# charliewatch.net
KiCad netlist of a schematic drawn in EAGLE
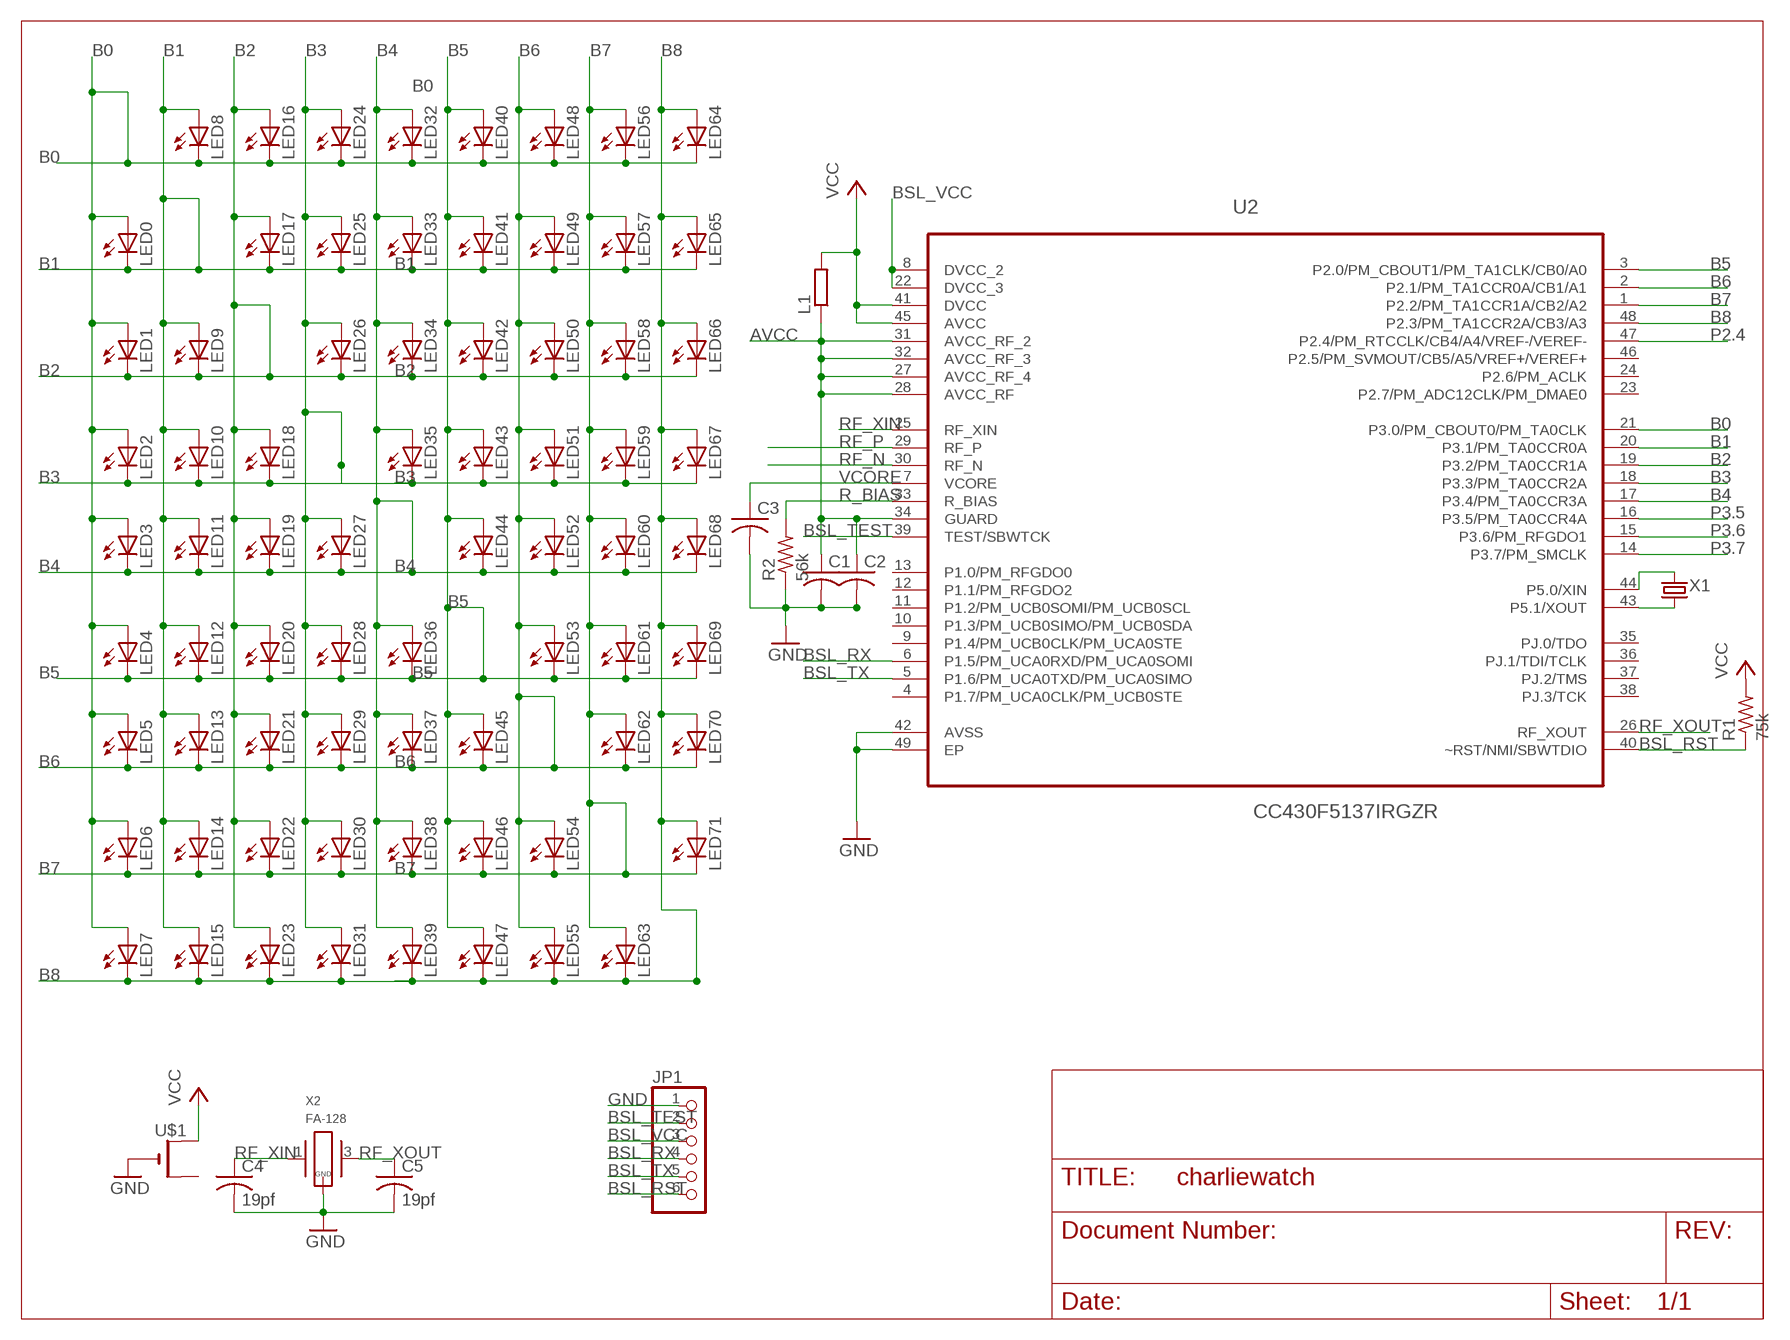
[diagram p0: schematic, sheet 1]

(export (version "E")
  (design (tool "Eeschema 10.0.6"))
  (components
    (comp (ref "C1")
      (value "C-USC0603")
      (footprint "eagle-import:C0603")
      (libsource (lib "eagle-import") (part "C-USC0603"))
    )
    (comp (ref "C2")
      (value "C-USC0603")
      (footprint "eagle-import:C0603")
      (libsource (lib "eagle-import") (part "C-USC0603"))
    )
    (comp (ref "C3")
      (value "C-USC0603")
      (footprint "eagle-import:C0603")
      (libsource (lib "eagle-import") (part "C-USC0603"))
    )
    (comp (ref "C4")
      (value "19pf")
      (footprint "eagle-import:C0603")
      (libsource (lib "eagle-import") (part "C-USC0603"))
    )
    (comp (ref "C5")
      (value "19pf")
      (footprint "eagle-import:C0603")
      (libsource (lib "eagle-import") (part "C-USC0603"))
    )
    (comp (ref "JP1")
      (value "PINHD-1X6LOCK")
      (footprint "eagle-import:1X06-BIGLOCK")
      (libsource (lib "eagle-import") (part "PINHD-1X6LOCK"))
    )
    (comp (ref "L1")
      (value "R-EU_R0603")
      (footprint "eagle-import:R0603")
      (libsource (lib "eagle-import") (part "R-EU_R0603"))
    )
    (comp (ref "LED0")
      (value "LEDCHIPLED_0603")
      (footprint "eagle-import:CHIPLED_0603")
      (libsource (lib "eagle-import") (part "LEDCHIPLED_0603"))
    )
    (comp (ref "LED1")
      (value "LEDCHIPLED_0603")
      (footprint "eagle-import:CHIPLED_0603")
      (libsource (lib "eagle-import") (part "LEDCHIPLED_0603"))
    )
    (comp (ref "LED2")
      (value "LEDCHIPLED_0603")
      (footprint "eagle-import:CHIPLED_0603")
      (libsource (lib "eagle-import") (part "LEDCHIPLED_0603"))
    )
    (comp (ref "LED3")
      (value "LEDCHIPLED_0603")
      (footprint "eagle-import:CHIPLED_0603")
      (libsource (lib "eagle-import") (part "LEDCHIPLED_0603"))
    )
    (comp (ref "LED4")
      (value "LEDCHIPLED_0603")
      (footprint "eagle-import:CHIPLED_0603")
      (libsource (lib "eagle-import") (part "LEDCHIPLED_0603"))
    )
    (comp (ref "LED5")
      (value "LEDCHIPLED_0603")
      (footprint "eagle-import:CHIPLED_0603")
      (libsource (lib "eagle-import") (part "LEDCHIPLED_0603"))
    )
    (comp (ref "LED6")
      (value "LEDCHIPLED_0603")
      (footprint "eagle-import:CHIPLED_0603")
      (libsource (lib "eagle-import") (part "LEDCHIPLED_0603"))
    )
    (comp (ref "LED7")
      (value "LEDCHIPLED_0603")
      (footprint "eagle-import:CHIPLED_0603")
      (libsource (lib "eagle-import") (part "LEDCHIPLED_0603"))
    )
    (comp (ref "LED8")
      (value "LEDCHIPLED_0603")
      (footprint "eagle-import:CHIPLED_0603")
      (libsource (lib "eagle-import") (part "LEDCHIPLED_0603"))
    )
    (comp (ref "LED9")
      (value "LEDCHIPLED_0603")
      (footprint "eagle-import:CHIPLED_0603")
      (libsource (lib "eagle-import") (part "LEDCHIPLED_0603"))
    )
    (comp (ref "LED10")
      (value "LEDCHIPLED_0603")
      (footprint "eagle-import:CHIPLED_0603")
      (libsource (lib "eagle-import") (part "LEDCHIPLED_0603"))
    )
    (comp (ref "LED11")
      (value "LEDCHIPLED_0603")
      (footprint "eagle-import:CHIPLED_0603")
      (libsource (lib "eagle-import") (part "LEDCHIPLED_0603"))
    )
    (comp (ref "LED12")
      (value "LEDCHIPLED_0603")
      (footprint "eagle-import:CHIPLED_0603")
      (libsource (lib "eagle-import") (part "LEDCHIPLED_0603"))
    )
    (comp (ref "LED13")
      (value "LEDCHIPLED_0603")
      (footprint "eagle-import:CHIPLED_0603")
      (libsource (lib "eagle-import") (part "LEDCHIPLED_0603"))
    )
    (comp (ref "LED14")
      (value "LEDCHIPLED_0603")
      (footprint "eagle-import:CHIPLED_0603")
      (libsource (lib "eagle-import") (part "LEDCHIPLED_0603"))
    )
    (comp (ref "LED15")
      (value "LEDCHIPLED_0603")
      (footprint "eagle-import:CHIPLED_0603")
      (libsource (lib "eagle-import") (part "LEDCHIPLED_0603"))
    )
    (comp (ref "LED16")
      (value "LEDCHIPLED_0603")
      (footprint "eagle-import:CHIPLED_0603")
      (libsource (lib "eagle-import") (part "LEDCHIPLED_0603"))
    )
    (comp (ref "LED17")
      (value "LEDCHIPLED_0603")
      (footprint "eagle-import:CHIPLED_0603")
      (libsource (lib "eagle-import") (part "LEDCHIPLED_0603"))
    )
    (comp (ref "LED18")
      (value "LEDCHIPLED_0603")
      (footprint "eagle-import:CHIPLED_0603")
      (libsource (lib "eagle-import") (part "LEDCHIPLED_0603"))
    )
    (comp (ref "LED19")
      (value "LEDCHIPLED_0603")
      (footprint "eagle-import:CHIPLED_0603")
      (libsource (lib "eagle-import") (part "LEDCHIPLED_0603"))
    )
    (comp (ref "LED20")
      (value "LEDCHIPLED_0603")
      (footprint "eagle-import:CHIPLED_0603")
      (libsource (lib "eagle-import") (part "LEDCHIPLED_0603"))
    )
    (comp (ref "LED21")
      (value "LEDCHIPLED_0603")
      (footprint "eagle-import:CHIPLED_0603")
      (libsource (lib "eagle-import") (part "LEDCHIPLED_0603"))
    )
    (comp (ref "LED22")
      (value "LEDCHIPLED_0603")
      (footprint "eagle-import:CHIPLED_0603")
      (libsource (lib "eagle-import") (part "LEDCHIPLED_0603"))
    )
    (comp (ref "LED23")
      (value "LEDCHIPLED_0603")
      (footprint "eagle-import:CHIPLED_0603")
      (libsource (lib "eagle-import") (part "LEDCHIPLED_0603"))
    )
    (comp (ref "LED24")
      (value "LEDCHIPLED_0603")
      (footprint "eagle-import:CHIPLED_0603")
      (libsource (lib "eagle-import") (part "LEDCHIPLED_0603"))
    )
    (comp (ref "LED25")
      (value "LEDCHIPLED_0603")
      (footprint "eagle-import:CHIPLED_0603")
      (libsource (lib "eagle-import") (part "LEDCHIPLED_0603"))
    )
    (comp (ref "LED26")
      (value "LEDCHIPLED_0603")
      (footprint "eagle-import:CHIPLED_0603")
      (libsource (lib "eagle-import") (part "LEDCHIPLED_0603"))
    )
    (comp (ref "LED27")
      (value "LEDCHIPLED_0603")
      (footprint "eagle-import:CHIPLED_0603")
      (libsource (lib "eagle-import") (part "LEDCHIPLED_0603"))
    )
    (comp (ref "LED28")
      (value "LEDCHIPLED_0603")
      (footprint "eagle-import:CHIPLED_0603")
      (libsource (lib "eagle-import") (part "LEDCHIPLED_0603"))
    )
    (comp (ref "LED29")
      (value "LEDCHIPLED_0603")
      (footprint "eagle-import:CHIPLED_0603")
      (libsource (lib "eagle-import") (part "LEDCHIPLED_0603"))
    )
    (comp (ref "LED30")
      (value "LEDCHIPLED_0603")
      (footprint "eagle-import:CHIPLED_0603")
      (libsource (lib "eagle-import") (part "LEDCHIPLED_0603"))
    )
    (comp (ref "LED31")
      (value "LEDCHIPLED_0603")
      (footprint "eagle-import:CHIPLED_0603")
      (libsource (lib "eagle-import") (part "LEDCHIPLED_0603"))
    )
    (comp (ref "LED32")
      (value "LEDCHIPLED_0603")
      (footprint "eagle-import:CHIPLED_0603")
      (libsource (lib "eagle-import") (part "LEDCHIPLED_0603"))
    )
    (comp (ref "LED33")
      (value "LEDCHIPLED_0603")
      (footprint "eagle-import:CHIPLED_0603")
      (libsource (lib "eagle-import") (part "LEDCHIPLED_0603"))
    )
    (comp (ref "LED34")
      (value "LEDCHIPLED_0603")
      (footprint "eagle-import:CHIPLED_0603")
      (libsource (lib "eagle-import") (part "LEDCHIPLED_0603"))
    )
    (comp (ref "LED35")
      (value "LEDCHIPLED_0603")
      (footprint "eagle-import:CHIPLED_0603")
      (libsource (lib "eagle-import") (part "LEDCHIPLED_0603"))
    )
    (comp (ref "LED36")
      (value "LEDCHIPLED_0603")
      (footprint "eagle-import:CHIPLED_0603")
      (libsource (lib "eagle-import") (part "LEDCHIPLED_0603"))
    )
    (comp (ref "LED37")
      (value "LEDCHIPLED_0603")
      (footprint "eagle-import:CHIPLED_0603")
      (libsource (lib "eagle-import") (part "LEDCHIPLED_0603"))
    )
    (comp (ref "LED38")
      (value "LEDCHIPLED_0603")
      (footprint "eagle-import:CHIPLED_0603")
      (libsource (lib "eagle-import") (part "LEDCHIPLED_0603"))
    )
    (comp (ref "LED39")
      (value "LEDCHIPLED_0603")
      (footprint "eagle-import:CHIPLED_0603")
      (libsource (lib "eagle-import") (part "LEDCHIPLED_0603"))
    )
    (comp (ref "LED40")
      (value "LEDCHIPLED_0603")
      (footprint "eagle-import:CHIPLED_0603")
      (libsource (lib "eagle-import") (part "LEDCHIPLED_0603"))
    )
    (comp (ref "LED41")
      (value "LEDCHIPLED_0603")
      (footprint "eagle-import:CHIPLED_0603")
      (libsource (lib "eagle-import") (part "LEDCHIPLED_0603"))
    )
    (comp (ref "LED42")
      (value "LEDCHIPLED_0603")
      (footprint "eagle-import:CHIPLED_0603")
      (libsource (lib "eagle-import") (part "LEDCHIPLED_0603"))
    )
    (comp (ref "LED43")
      (value "LEDCHIPLED_0603")
      (footprint "eagle-import:CHIPLED_0603")
      (libsource (lib "eagle-import") (part "LEDCHIPLED_0603"))
    )
    (comp (ref "LED44")
      (value "LEDCHIPLED_0603")
      (footprint "eagle-import:CHIPLED_0603")
      (libsource (lib "eagle-import") (part "LEDCHIPLED_0603"))
    )
    (comp (ref "LED45")
      (value "LEDCHIPLED_0603")
      (footprint "eagle-import:CHIPLED_0603")
      (libsource (lib "eagle-import") (part "LEDCHIPLED_0603"))
    )
    (comp (ref "LED46")
      (value "LEDCHIPLED_0603")
      (footprint "eagle-import:CHIPLED_0603")
      (libsource (lib "eagle-import") (part "LEDCHIPLED_0603"))
    )
    (comp (ref "LED47")
      (value "LEDCHIPLED_0603")
      (footprint "eagle-import:CHIPLED_0603")
      (libsource (lib "eagle-import") (part "LEDCHIPLED_0603"))
    )
    (comp (ref "LED48")
      (value "LEDCHIPLED_0603")
      (footprint "eagle-import:CHIPLED_0603")
      (libsource (lib "eagle-import") (part "LEDCHIPLED_0603"))
    )
    (comp (ref "LED49")
      (value "LEDCHIPLED_0603")
      (footprint "eagle-import:CHIPLED_0603")
      (libsource (lib "eagle-import") (part "LEDCHIPLED_0603"))
    )
    (comp (ref "LED50")
      (value "LEDCHIPLED_0603")
      (footprint "eagle-import:CHIPLED_0603")
      (libsource (lib "eagle-import") (part "LEDCHIPLED_0603"))
    )
    (comp (ref "LED51")
      (value "LEDCHIPLED_0603")
      (footprint "eagle-import:CHIPLED_0603")
      (libsource (lib "eagle-import") (part "LEDCHIPLED_0603"))
    )
    (comp (ref "LED52")
      (value "LEDCHIPLED_0603")
      (footprint "eagle-import:CHIPLED_0603")
      (libsource (lib "eagle-import") (part "LEDCHIPLED_0603"))
    )
    (comp (ref "LED53")
      (value "LEDCHIPLED_0603")
      (footprint "eagle-import:CHIPLED_0603")
      (libsource (lib "eagle-import") (part "LEDCHIPLED_0603"))
    )
    (comp (ref "LED54")
      (value "LEDCHIPLED_0603")
      (footprint "eagle-import:CHIPLED_0603")
      (libsource (lib "eagle-import") (part "LEDCHIPLED_0603"))
    )
    (comp (ref "LED55")
      (value "LEDCHIPLED_0603")
      (footprint "eagle-import:CHIPLED_0603")
      (libsource (lib "eagle-import") (part "LEDCHIPLED_0603"))
    )
    (comp (ref "LED56")
      (value "LEDCHIPLED_0603")
      (footprint "eagle-import:CHIPLED_0603")
      (libsource (lib "eagle-import") (part "LEDCHIPLED_0603"))
    )
    (comp (ref "LED57")
      (value "LEDCHIPLED_0603")
      (footprint "eagle-import:CHIPLED_0603")
      (libsource (lib "eagle-import") (part "LEDCHIPLED_0603"))
    )
    (comp (ref "LED58")
      (value "LEDCHIPLED_0603")
      (footprint "eagle-import:CHIPLED_0603")
      (libsource (lib "eagle-import") (part "LEDCHIPLED_0603"))
    )
    (comp (ref "LED59")
      (value "LEDCHIPLED_0603")
      (footprint "eagle-import:CHIPLED_0603")
      (libsource (lib "eagle-import") (part "LEDCHIPLED_0603"))
    )
    (comp (ref "LED60")
      (value "LEDCHIPLED_0603")
      (footprint "eagle-import:CHIPLED_0603")
      (libsource (lib "eagle-import") (part "LEDCHIPLED_0603"))
    )
    (comp (ref "LED61")
      (value "LEDCHIPLED_0603")
      (footprint "eagle-import:CHIPLED_0603")
      (libsource (lib "eagle-import") (part "LEDCHIPLED_0603"))
    )
    (comp (ref "LED62")
      (value "LEDCHIPLED_0603")
      (footprint "eagle-import:CHIPLED_0603")
      (libsource (lib "eagle-import") (part "LEDCHIPLED_0603"))
    )
    (comp (ref "LED63")
      (value "LEDCHIPLED_0603")
      (footprint "eagle-import:CHIPLED_0603")
      (libsource (lib "eagle-import") (part "LEDCHIPLED_0603"))
    )
    (comp (ref "LED64")
      (value "LEDCHIPLED_0603")
      (footprint "eagle-import:CHIPLED_0603")
      (libsource (lib "eagle-import") (part "LEDCHIPLED_0603"))
    )
    (comp (ref "LED65")
      (value "LEDCHIPLED_0603")
      (footprint "eagle-import:CHIPLED_0603")
      (libsource (lib "eagle-import") (part "LEDCHIPLED_0603"))
    )
    (comp (ref "LED66")
      (value "LEDCHIPLED_0603")
      (footprint "eagle-import:CHIPLED_0603")
      (libsource (lib "eagle-import") (part "LEDCHIPLED_0603"))
    )
    (comp (ref "LED67")
      (value "LEDCHIPLED_0603")
      (footprint "eagle-import:CHIPLED_0603")
      (libsource (lib "eagle-import") (part "LEDCHIPLED_0603"))
    )
    (comp (ref "LED68")
      (value "LEDCHIPLED_0603")
      (footprint "eagle-import:CHIPLED_0603")
      (libsource (lib "eagle-import") (part "LEDCHIPLED_0603"))
    )
    (comp (ref "LED69")
      (value "LEDCHIPLED_0603")
      (footprint "eagle-import:CHIPLED_0603")
      (libsource (lib "eagle-import") (part "LEDCHIPLED_0603"))
    )
    (comp (ref "LED70")
      (value "LEDCHIPLED_0603")
      (footprint "eagle-import:CHIPLED_0603")
      (libsource (lib "eagle-import") (part "LEDCHIPLED_0603"))
    )
    (comp (ref "LED71")
      (value "LEDCHIPLED_0603")
      (footprint "eagle-import:CHIPLED_0603")
      (libsource (lib "eagle-import") (part "LEDCHIPLED_0603"))
    )
    (comp (ref "R1")
      (value "75k")
      (footprint "eagle-import:R0603")
      (libsource (lib "eagle-import") (part "R-US_R0603"))
    )
    (comp (ref "R2")
      (value "56k")
      (footprint "eagle-import:R0603")
      (libsource (lib "eagle-import") (part "R-US_R0603"))
    )
    (comp (ref "U$1")
      (value "CR2032SMT")
      (footprint "eagle-import:CR2032-SMD")
      (libsource (lib "eagle-import") (part "CR2032SMT"))
    )
    (comp (ref "U2")
      (value "CC430F5137IRGZR")
      (footprint "eagle-import:QFN50P700X700X100-49N")
      (libsource (lib "eagle-import") (part "CC430F5137IRGZR"))
    )
    (comp (ref "X1")
      (value "CRYSTALS-NOGND-IQXC-25")
      (footprint "eagle-import:2.0X1.2-2PAD")
      (libsource (lib "eagle-import") (part "CRYSTALS-NOGND-IQXC-25"))
    )
    (comp (ref "X2")
      (value "FA-128")
      (footprint "eagle-import:FA-128")
      (libsource (lib "eagle-import") (part "FA-128"))
    )
  )
  (nets
    (net (code "1") (name "/AVCC") (class "Default")
      (node (ref "C1") (pin "1") (pinfunction "1_1") (pintype "passive"))
      (node (ref "C2") (pin "1") (pinfunction "1_1") (pintype "passive"))
      (node (ref "L1") (pin "1") (pinfunction "1_1") (pintype "passive"))
      (node (ref "U2") (pin "27") (pinfunction "AVCC_RF_4_27") (pintype "power_in"))
      (node (ref "U2") (pin "28") (pinfunction "AVCC_RF_28") (pintype "power_in"))
      (node (ref "U2") (pin "31") (pinfunction "AVCC_RF_2_31") (pintype "power_in"))
      (node (ref "U2") (pin "32") (pinfunction "AVCC_RF_3_32") (pintype "power_in"))
      (node (ref "U2") (pin "34") (pinfunction "GUARD_34") (pintype "input"))
    )
    (net (code "2") (name "/B0") (class "Default")
      (node (ref "LED0") (pin "A") (pinfunction "A_A") (pintype "passive"))
      (node (ref "LED1") (pin "A") (pinfunction "A_A") (pintype "passive"))
      (node (ref "LED16") (pin "C") (pinfunction "C_C") (pintype "passive"))
      (node (ref "LED2") (pin "A") (pinfunction "A_A") (pintype "passive"))
      (node (ref "LED24") (pin "C") (pinfunction "C_C") (pintype "passive"))
      (node (ref "LED3") (pin "A") (pinfunction "A_A") (pintype "passive"))
      (node (ref "LED32") (pin "C") (pinfunction "C_C") (pintype "passive"))
      (node (ref "LED4") (pin "A") (pinfunction "A_A") (pintype "passive"))
      (node (ref "LED40") (pin "C") (pinfunction "C_C") (pintype "passive"))
      (node (ref "LED48") (pin "C") (pinfunction "C_C") (pintype "passive"))
      (node (ref "LED5") (pin "A") (pinfunction "A_A") (pintype "passive"))
      (node (ref "LED56") (pin "C") (pinfunction "C_C") (pintype "passive"))
      (node (ref "LED6") (pin "A") (pinfunction "A_A") (pintype "passive"))
      (node (ref "LED64") (pin "C") (pinfunction "C_C") (pintype "passive"))
      (node (ref "LED7") (pin "A") (pinfunction "A_A") (pintype "passive"))
      (node (ref "LED8") (pin "C") (pinfunction "C_C") (pintype "passive"))
      (node (ref "U2") (pin "21") (pinfunction "P3.0/PM_CBOUT0/PM_TA0CLK_21") (pintype "bidirectional"))
    )
    (net (code "3") (name "/B1") (class "Default")
      (node (ref "LED0") (pin "C") (pinfunction "C_C") (pintype "passive"))
      (node (ref "LED10") (pin "A") (pinfunction "A_A") (pintype "passive"))
      (node (ref "LED11") (pin "A") (pinfunction "A_A") (pintype "passive"))
      (node (ref "LED12") (pin "A") (pinfunction "A_A") (pintype "passive"))
      (node (ref "LED13") (pin "A") (pinfunction "A_A") (pintype "passive"))
      (node (ref "LED14") (pin "A") (pinfunction "A_A") (pintype "passive"))
      (node (ref "LED15") (pin "A") (pinfunction "A_A") (pintype "passive"))
      (node (ref "LED17") (pin "C") (pinfunction "C_C") (pintype "passive"))
      (node (ref "LED25") (pin "C") (pinfunction "C_C") (pintype "passive"))
      (node (ref "LED33") (pin "C") (pinfunction "C_C") (pintype "passive"))
      (node (ref "LED41") (pin "C") (pinfunction "C_C") (pintype "passive"))
      (node (ref "LED49") (pin "C") (pinfunction "C_C") (pintype "passive"))
      (node (ref "LED57") (pin "C") (pinfunction "C_C") (pintype "passive"))
      (node (ref "LED65") (pin "C") (pinfunction "C_C") (pintype "passive"))
      (node (ref "LED8") (pin "A") (pinfunction "A_A") (pintype "passive"))
      (node (ref "LED9") (pin "A") (pinfunction "A_A") (pintype "passive"))
      (node (ref "U2") (pin "20") (pinfunction "P3.1/PM_TA0CCR0A_20") (pintype "bidirectional"))
    )
    (net (code "4") (name "/B2") (class "Default")
      (node (ref "LED1") (pin "C") (pinfunction "C_C") (pintype "passive"))
      (node (ref "LED16") (pin "A") (pinfunction "A_A") (pintype "passive"))
      (node (ref "LED17") (pin "A") (pinfunction "A_A") (pintype "passive"))
      (node (ref "LED18") (pin "A") (pinfunction "A_A") (pintype "passive"))
      (node (ref "LED19") (pin "A") (pinfunction "A_A") (pintype "passive"))
      (node (ref "LED20") (pin "A") (pinfunction "A_A") (pintype "passive"))
      (node (ref "LED21") (pin "A") (pinfunction "A_A") (pintype "passive"))
      (node (ref "LED22") (pin "A") (pinfunction "A_A") (pintype "passive"))
      (node (ref "LED23") (pin "A") (pinfunction "A_A") (pintype "passive"))
      (node (ref "LED26") (pin "C") (pinfunction "C_C") (pintype "passive"))
      (node (ref "LED34") (pin "C") (pinfunction "C_C") (pintype "passive"))
      (node (ref "LED42") (pin "C") (pinfunction "C_C") (pintype "passive"))
      (node (ref "LED50") (pin "C") (pinfunction "C_C") (pintype "passive"))
      (node (ref "LED58") (pin "C") (pinfunction "C_C") (pintype "passive"))
      (node (ref "LED66") (pin "C") (pinfunction "C_C") (pintype "passive"))
      (node (ref "LED9") (pin "C") (pinfunction "C_C") (pintype "passive"))
      (node (ref "U2") (pin "19") (pinfunction "P3.2/PM_TA0CCR1A_19") (pintype "bidirectional"))
    )
    (net (code "5") (name "/B3") (class "Default")
      (node (ref "LED10") (pin "C") (pinfunction "C_C") (pintype "passive"))
      (node (ref "LED18") (pin "C") (pinfunction "C_C") (pintype "passive"))
      (node (ref "LED2") (pin "C") (pinfunction "C_C") (pintype "passive"))
      (node (ref "LED24") (pin "A") (pinfunction "A_A") (pintype "passive"))
      (node (ref "LED25") (pin "A") (pinfunction "A_A") (pintype "passive"))
      (node (ref "LED26") (pin "A") (pinfunction "A_A") (pintype "passive"))
      (node (ref "LED27") (pin "A") (pinfunction "A_A") (pintype "passive"))
      (node (ref "LED28") (pin "A") (pinfunction "A_A") (pintype "passive"))
      (node (ref "LED29") (pin "A") (pinfunction "A_A") (pintype "passive"))
      (node (ref "LED30") (pin "A") (pinfunction "A_A") (pintype "passive"))
      (node (ref "LED31") (pin "A") (pinfunction "A_A") (pintype "passive"))
      (node (ref "LED35") (pin "C") (pinfunction "C_C") (pintype "passive"))
      (node (ref "LED43") (pin "C") (pinfunction "C_C") (pintype "passive"))
      (node (ref "LED51") (pin "C") (pinfunction "C_C") (pintype "passive"))
      (node (ref "LED59") (pin "C") (pinfunction "C_C") (pintype "passive"))
      (node (ref "LED67") (pin "C") (pinfunction "C_C") (pintype "passive"))
      (node (ref "U2") (pin "18") (pinfunction "P3.3/PM_TA0CCR2A_18") (pintype "bidirectional"))
    )
    (net (code "6") (name "/B4") (class "Default")
      (node (ref "LED11") (pin "C") (pinfunction "C_C") (pintype "passive"))
      (node (ref "LED19") (pin "C") (pinfunction "C_C") (pintype "passive"))
      (node (ref "LED27") (pin "C") (pinfunction "C_C") (pintype "passive"))
      (node (ref "LED3") (pin "C") (pinfunction "C_C") (pintype "passive"))
      (node (ref "LED32") (pin "A") (pinfunction "A_A") (pintype "passive"))
      (node (ref "LED33") (pin "A") (pinfunction "A_A") (pintype "passive"))
      (node (ref "LED34") (pin "A") (pinfunction "A_A") (pintype "passive"))
      (node (ref "LED35") (pin "A") (pinfunction "A_A") (pintype "passive"))
      (node (ref "LED36") (pin "A") (pinfunction "A_A") (pintype "passive"))
      (node (ref "LED37") (pin "A") (pinfunction "A_A") (pintype "passive"))
      (node (ref "LED38") (pin "A") (pinfunction "A_A") (pintype "passive"))
      (node (ref "LED39") (pin "A") (pinfunction "A_A") (pintype "passive"))
      (node (ref "LED44") (pin "C") (pinfunction "C_C") (pintype "passive"))
      (node (ref "LED52") (pin "C") (pinfunction "C_C") (pintype "passive"))
      (node (ref "LED60") (pin "C") (pinfunction "C_C") (pintype "passive"))
      (node (ref "LED68") (pin "C") (pinfunction "C_C") (pintype "passive"))
      (node (ref "U2") (pin "17") (pinfunction "P3.4/PM_TA0CCR3A_17") (pintype "bidirectional"))
    )
    (net (code "7") (name "/B5") (class "Default")
      (node (ref "LED12") (pin "C") (pinfunction "C_C") (pintype "passive"))
      (node (ref "LED20") (pin "C") (pinfunction "C_C") (pintype "passive"))
      (node (ref "LED28") (pin "C") (pinfunction "C_C") (pintype "passive"))
      (node (ref "LED36") (pin "C") (pinfunction "C_C") (pintype "passive"))
      (node (ref "LED4") (pin "C") (pinfunction "C_C") (pintype "passive"))
      (node (ref "LED40") (pin "A") (pinfunction "A_A") (pintype "passive"))
      (node (ref "LED41") (pin "A") (pinfunction "A_A") (pintype "passive"))
      (node (ref "LED42") (pin "A") (pinfunction "A_A") (pintype "passive"))
      (node (ref "LED43") (pin "A") (pinfunction "A_A") (pintype "passive"))
      (node (ref "LED44") (pin "A") (pinfunction "A_A") (pintype "passive"))
      (node (ref "LED45") (pin "A") (pinfunction "A_A") (pintype "passive"))
      (node (ref "LED46") (pin "A") (pinfunction "A_A") (pintype "passive"))
      (node (ref "LED47") (pin "A") (pinfunction "A_A") (pintype "passive"))
      (node (ref "LED53") (pin "C") (pinfunction "C_C") (pintype "passive"))
      (node (ref "LED61") (pin "C") (pinfunction "C_C") (pintype "passive"))
      (node (ref "LED69") (pin "C") (pinfunction "C_C") (pintype "passive"))
      (node (ref "U2") (pin "3") (pinfunction "P2.0/PM_CBOUT1/PM_TA1CLK/CB0/A0_3") (pintype "bidirectional"))
    )
    (net (code "8") (name "/B6") (class "Default")
      (node (ref "LED13") (pin "C") (pinfunction "C_C") (pintype "passive"))
      (node (ref "LED21") (pin "C") (pinfunction "C_C") (pintype "passive"))
      (node (ref "LED29") (pin "C") (pinfunction "C_C") (pintype "passive"))
      (node (ref "LED37") (pin "C") (pinfunction "C_C") (pintype "passive"))
      (node (ref "LED45") (pin "C") (pinfunction "C_C") (pintype "passive"))
      (node (ref "LED48") (pin "A") (pinfunction "A_A") (pintype "passive"))
      (node (ref "LED49") (pin "A") (pinfunction "A_A") (pintype "passive"))
      (node (ref "LED5") (pin "C") (pinfunction "C_C") (pintype "passive"))
      (node (ref "LED50") (pin "A") (pinfunction "A_A") (pintype "passive"))
      (node (ref "LED51") (pin "A") (pinfunction "A_A") (pintype "passive"))
      (node (ref "LED52") (pin "A") (pinfunction "A_A") (pintype "passive"))
      (node (ref "LED53") (pin "A") (pinfunction "A_A") (pintype "passive"))
      (node (ref "LED54") (pin "A") (pinfunction "A_A") (pintype "passive"))
      (node (ref "LED55") (pin "A") (pinfunction "A_A") (pintype "passive"))
      (node (ref "LED62") (pin "C") (pinfunction "C_C") (pintype "passive"))
      (node (ref "LED70") (pin "C") (pinfunction "C_C") (pintype "passive"))
      (node (ref "U2") (pin "2") (pinfunction "P2.1/PM_TA1CCR0A/CB1/A1_2") (pintype "bidirectional"))
    )
    (net (code "9") (name "/B7") (class "Default")
      (node (ref "LED14") (pin "C") (pinfunction "C_C") (pintype "passive"))
      (node (ref "LED22") (pin "C") (pinfunction "C_C") (pintype "passive"))
      (node (ref "LED30") (pin "C") (pinfunction "C_C") (pintype "passive"))
      (node (ref "LED38") (pin "C") (pinfunction "C_C") (pintype "passive"))
      (node (ref "LED46") (pin "C") (pinfunction "C_C") (pintype "passive"))
      (node (ref "LED54") (pin "C") (pinfunction "C_C") (pintype "passive"))
      (node (ref "LED56") (pin "A") (pinfunction "A_A") (pintype "passive"))
      (node (ref "LED57") (pin "A") (pinfunction "A_A") (pintype "passive"))
      (node (ref "LED58") (pin "A") (pinfunction "A_A") (pintype "passive"))
      (node (ref "LED59") (pin "A") (pinfunction "A_A") (pintype "passive"))
      (node (ref "LED6") (pin "C") (pinfunction "C_C") (pintype "passive"))
      (node (ref "LED60") (pin "A") (pinfunction "A_A") (pintype "passive"))
      (node (ref "LED61") (pin "A") (pinfunction "A_A") (pintype "passive"))
      (node (ref "LED62") (pin "A") (pinfunction "A_A") (pintype "passive"))
      (node (ref "LED63") (pin "A") (pinfunction "A_A") (pintype "passive"))
      (node (ref "LED71") (pin "C") (pinfunction "C_C") (pintype "passive"))
      (node (ref "U2") (pin "1") (pinfunction "P2.2/PM_TA1CCR1A/CB2/A2_1") (pintype "bidirectional"))
    )
    (net (code "10") (name "/B8") (class "Default")
      (node (ref "LED15") (pin "C") (pinfunction "C_C") (pintype "passive"))
      (node (ref "LED23") (pin "C") (pinfunction "C_C") (pintype "passive"))
      (node (ref "LED31") (pin "C") (pinfunction "C_C") (pintype "passive"))
      (node (ref "LED39") (pin "C") (pinfunction "C_C") (pintype "passive"))
      (node (ref "LED47") (pin "C") (pinfunction "C_C") (pintype "passive"))
      (node (ref "LED55") (pin "C") (pinfunction "C_C") (pintype "passive"))
      (node (ref "LED63") (pin "C") (pinfunction "C_C") (pintype "passive"))
      (node (ref "LED64") (pin "A") (pinfunction "A_A") (pintype "passive"))
      (node (ref "LED65") (pin "A") (pinfunction "A_A") (pintype "passive"))
      (node (ref "LED66") (pin "A") (pinfunction "A_A") (pintype "passive"))
      (node (ref "LED67") (pin "A") (pinfunction "A_A") (pintype "passive"))
      (node (ref "LED68") (pin "A") (pinfunction "A_A") (pintype "passive"))
      (node (ref "LED69") (pin "A") (pinfunction "A_A") (pintype "passive"))
      (node (ref "LED7") (pin "C") (pinfunction "C_C") (pintype "passive"))
      (node (ref "LED70") (pin "A") (pinfunction "A_A") (pintype "passive"))
      (node (ref "LED71") (pin "A") (pinfunction "A_A") (pintype "passive"))
      (node (ref "U2") (pin "48") (pinfunction "P2.3/PM_TA1CCR2A/CB3/A3_48") (pintype "bidirectional"))
    )
    (net (code "11") (name "/BSL_RST") (class "Default")
      (node (ref "JP1") (pin "6") (pinfunction "6_6") (pintype "passive"))
      (node (ref "R1") (pin "1") (pinfunction "1_1") (pintype "passive"))
      (node (ref "U2") (pin "40") (pinfunction "~{RST/NMI/SBWTDIO}_40") (pintype "bidirectional"))
    )
    (net (code "12") (name "/BSL_RX") (class "Default")
      (node (ref "JP1") (pin "4") (pinfunction "4_4") (pintype "passive"))
      (node (ref "U2") (pin "6") (pinfunction "P1.5/PM_UCA0RXD/PM_UCA0SOMI_6") (pintype "bidirectional"))
    )
    (net (code "13") (name "/BSL_TEST") (class "Default")
      (node (ref "JP1") (pin "2") (pinfunction "2_2") (pintype "passive"))
      (node (ref "U2") (pin "39") (pinfunction "TEST/SBWTCK_39") (pintype "input"))
    )
    (net (code "14") (name "/BSL_TX") (class "Default")
      (node (ref "JP1") (pin "5") (pinfunction "5_5") (pintype "passive"))
      (node (ref "U2") (pin "5") (pinfunction "P1.6/PM_UCA0TXD/PM_UCA0SIMO_5") (pintype "bidirectional"))
    )
    (net (code "15") (name "/BSL_VCC") (class "Default")
      (node (ref "JP1") (pin "3") (pinfunction "3_3") (pintype "passive"))
      (node (ref "U2") (pin "22") (pinfunction "DVCC_3_22") (pintype "power_in"))
      (node (ref "U2") (pin "8") (pinfunction "DVCC_2_8") (pintype "power_in"))
    )
    (net (code "16") (name "/P2.4") (class "Default")
      (node (ref "U2") (pin "47") (pinfunction "P2.4/PM_RTCCLK/CB4/A4/VREF-/VEREF-_47") (pintype "bidirectional"))
    )
    (net (code "17") (name "/P3.5") (class "Default")
      (node (ref "U2") (pin "16") (pinfunction "P3.5/PM_TA0CCR4A_16") (pintype "bidirectional"))
    )
    (net (code "18") (name "/P3.6") (class "Default")
      (node (ref "U2") (pin "15") (pinfunction "P3.6/PM_RFGDO1_15") (pintype "bidirectional"))
    )
    (net (code "19") (name "/P3.7") (class "Default")
      (node (ref "U2") (pin "14") (pinfunction "P3.7/PM_SMCLK_14") (pintype "bidirectional"))
    )
    (net (code "20") (name "/RF_N") (class "Default")
      (node (ref "U2") (pin "30") (pinfunction "RF_N_30") (pintype "bidirectional"))
    )
    (net (code "21") (name "/RF_P") (class "Default")
      (node (ref "U2") (pin "29") (pinfunction "RF_P_29") (pintype "bidirectional"))
    )
    (net (code "22") (name "/RF_XIN") (class "Default")
      (node (ref "C4") (pin "1") (pinfunction "1_1") (pintype "passive"))
      (node (ref "U2") (pin "25") (pinfunction "RF_XIN_25") (pintype "input"))
      (node (ref "X2") (pin "1") (pinfunction "1_1") (pintype "bidirectional"))
    )
    (net (code "23") (name "/RF_XOUT") (class "Default")
      (node (ref "C5") (pin "1") (pinfunction "1_1") (pintype "passive"))
      (node (ref "U2") (pin "26") (pinfunction "RF_XOUT_26") (pintype "output"))
      (node (ref "X2") (pin "3") (pinfunction "2_3") (pintype "bidirectional"))
    )
    (net (code "24") (name "/R_BIAS") (class "Default")
      (node (ref "R2") (pin "2") (pinfunction "2_2") (pintype "passive"))
      (node (ref "U2") (pin "33") (pinfunction "R_BIAS_33") (pintype "input"))
    )
    (net (code "25") (name "/VCORE") (class "Default")
      (node (ref "C3") (pin "1") (pinfunction "1_1") (pintype "passive"))
      (node (ref "U2") (pin "7") (pinfunction "VCORE_7") (pintype "input"))
    )
    (net (code "26") (name "GND") (class "Default")
      (node (ref "C1") (pin "2") (pinfunction "2_2") (pintype "passive"))
      (node (ref "C2") (pin "2") (pinfunction "2_2") (pintype "passive"))
      (node (ref "C3") (pin "2") (pinfunction "2_2") (pintype "passive"))
      (node (ref "C4") (pin "2") (pinfunction "2_2") (pintype "passive"))
      (node (ref "C5") (pin "2") (pinfunction "2_2") (pintype "passive"))
      (node (ref "JP1") (pin "1") (pinfunction "1_1") (pintype "passive"))
      (node (ref "R2") (pin "1") (pinfunction "1_1") (pintype "passive"))
      (node (ref "U$1") (pin "-") (pinfunction "-_-") (pintype "passive"))
      (node (ref "U2") (pin "42") (pinfunction "AVSS_42") (pintype "passive"))
      (node (ref "U2") (pin "49") (pinfunction "EP_49") (pintype "passive"))
      (node (ref "X2") (pin "2") (pinfunction "GND_2") (pintype "bidirectional"))
      (node (ref "X2") (pin "4") (pinfunction "GND_4") (pintype "bidirectional"))
    )
    (net (code "27") (name "Net-(U2-P5.0{slash}XIN)") (class "Default")
      (node (ref "U2") (pin "44") (pinfunction "P5.0/XIN_44") (pintype "bidirectional"))
      (node (ref "X1") (pin "2") (pinfunction "2_2") (pintype "passive"))
    )
    (net (code "28") (name "Net-(U2-P5.1{slash}XOUT)") (class "Default")
      (node (ref "U2") (pin "43") (pinfunction "P5.1/XOUT_43") (pintype "bidirectional"))
      (node (ref "X1") (pin "1") (pinfunction "1_1") (pintype "passive"))
    )
    (net (code "29") (name "VCC") (class "Default")
      (node (ref "L1") (pin "2") (pinfunction "2_2") (pintype "passive"))
      (node (ref "R1") (pin "2") (pinfunction "2_2") (pintype "passive"))
      (node (ref "U$1") (pin "+$1") (pinfunction "+_+$1") (pintype "passive"))
      (node (ref "U2") (pin "41") (pinfunction "DVCC_41") (pintype "power_in"))
      (node (ref "U2") (pin "45") (pinfunction "AVCC_45") (pintype "power_in"))
    )
    (net (code "30") (name "unconnected-(U$1-+1-Pad+$2)") (class "Default")
      (node (ref "U$1") (pin "+$2") (pinfunction "+1_+$2") (pintype "passive"))
    )
    (net (code "31") (name "unconnected-(U2-P1.0{slash}PM_RFGDO0-Pad13)") (class "Default")
      (node (ref "U2") (pin "13") (pinfunction "P1.0/PM_RFGDO0_13") (pintype "bidirectional"))
    )
    (net (code "32") (name "unconnected-(U2-P1.1{slash}PM_RFGDO2-Pad12)") (class "Default")
      (node (ref "U2") (pin "12") (pinfunction "P1.1/PM_RFGDO2_12") (pintype "bidirectional"))
    )
    (net (code "33") (name "unconnected-(U2-P1.2{slash}PM_UCB0SOMI{slash}PM_UCB0SCL-Pad11)") (class "Default")
      (node (ref "U2") (pin "11") (pinfunction "P1.2/PM_UCB0SOMI/PM_UCB0SCL_11") (pintype "bidirectional"))
    )
    (net (code "34") (name "unconnected-(U2-P1.3{slash}PM_UCB0SIMO{slash}PM_UCB0SDA-Pad10)") (class "Default")
      (node (ref "U2") (pin "10") (pinfunction "P1.3/PM_UCB0SIMO/PM_UCB0SDA_10") (pintype "bidirectional"))
    )
    (net (code "35") (name "unconnected-(U2-P1.4{slash}PM_UCB0CLK{slash}PM_UCA0STE-Pad9)") (class "Default")
      (node (ref "U2") (pin "9") (pinfunction "P1.4/PM_UCB0CLK/PM_UCA0STE_9") (pintype "bidirectional"))
    )
    (net (code "36") (name "unconnected-(U2-P1.7{slash}PM_UCA0CLK{slash}PM_UCB0STE-Pad4)") (class "Default")
      (node (ref "U2") (pin "4") (pinfunction "P1.7/PM_UCA0CLK/PM_UCB0STE_4") (pintype "bidirectional"))
    )
    (net (code "37") (name "unconnected-(U2-P2.5{slash}PM_SVMOUT{slash}CB5{slash}A5{slash}VREF+{slash}VEREF+-Pad46)") (class "Default")
      (node (ref "U2") (pin "46") (pinfunction "P2.5/PM_SVMOUT/CB5/A5/VREF+/VEREF+_46") (pintype "bidirectional"))
    )
    (net (code "38") (name "unconnected-(U2-P2.6{slash}PM_ACLK-Pad24)") (class "Default")
      (node (ref "U2") (pin "24") (pinfunction "P2.6/PM_ACLK_24") (pintype "bidirectional"))
    )
    (net (code "39") (name "unconnected-(U2-P2.7{slash}PM_ADC12CLK{slash}PM_DMAE0-Pad23)") (class "Default")
      (node (ref "U2") (pin "23") (pinfunction "P2.7/PM_ADC12CLK/PM_DMAE0_23") (pintype "bidirectional"))
    )
    (net (code "40") (name "unconnected-(U2-PJ.0{slash}TDO-Pad35)") (class "Default")
      (node (ref "U2") (pin "35") (pinfunction "PJ.0/TDO_35") (pintype "bidirectional"))
    )
    (net (code "41") (name "unconnected-(U2-PJ.1{slash}TDI{slash}TCLK-Pad36)") (class "Default")
      (node (ref "U2") (pin "36") (pinfunction "PJ.1/TDI/TCLK_36") (pintype "bidirectional"))
    )
    (net (code "42") (name "unconnected-(U2-PJ.2{slash}TMS-Pad37)") (class "Default")
      (node (ref "U2") (pin "37") (pinfunction "PJ.2/TMS_37") (pintype "bidirectional"))
    )
    (net (code "43") (name "unconnected-(U2-PJ.3{slash}TCK-Pad38)") (class "Default")
      (node (ref "U2") (pin "38") (pinfunction "PJ.3/TCK_38") (pintype "bidirectional"))
    )
  )
)
